# ART-Pi_H750_Peripherals.net
KiCad netlist of a schematic drawn in Altium Designer
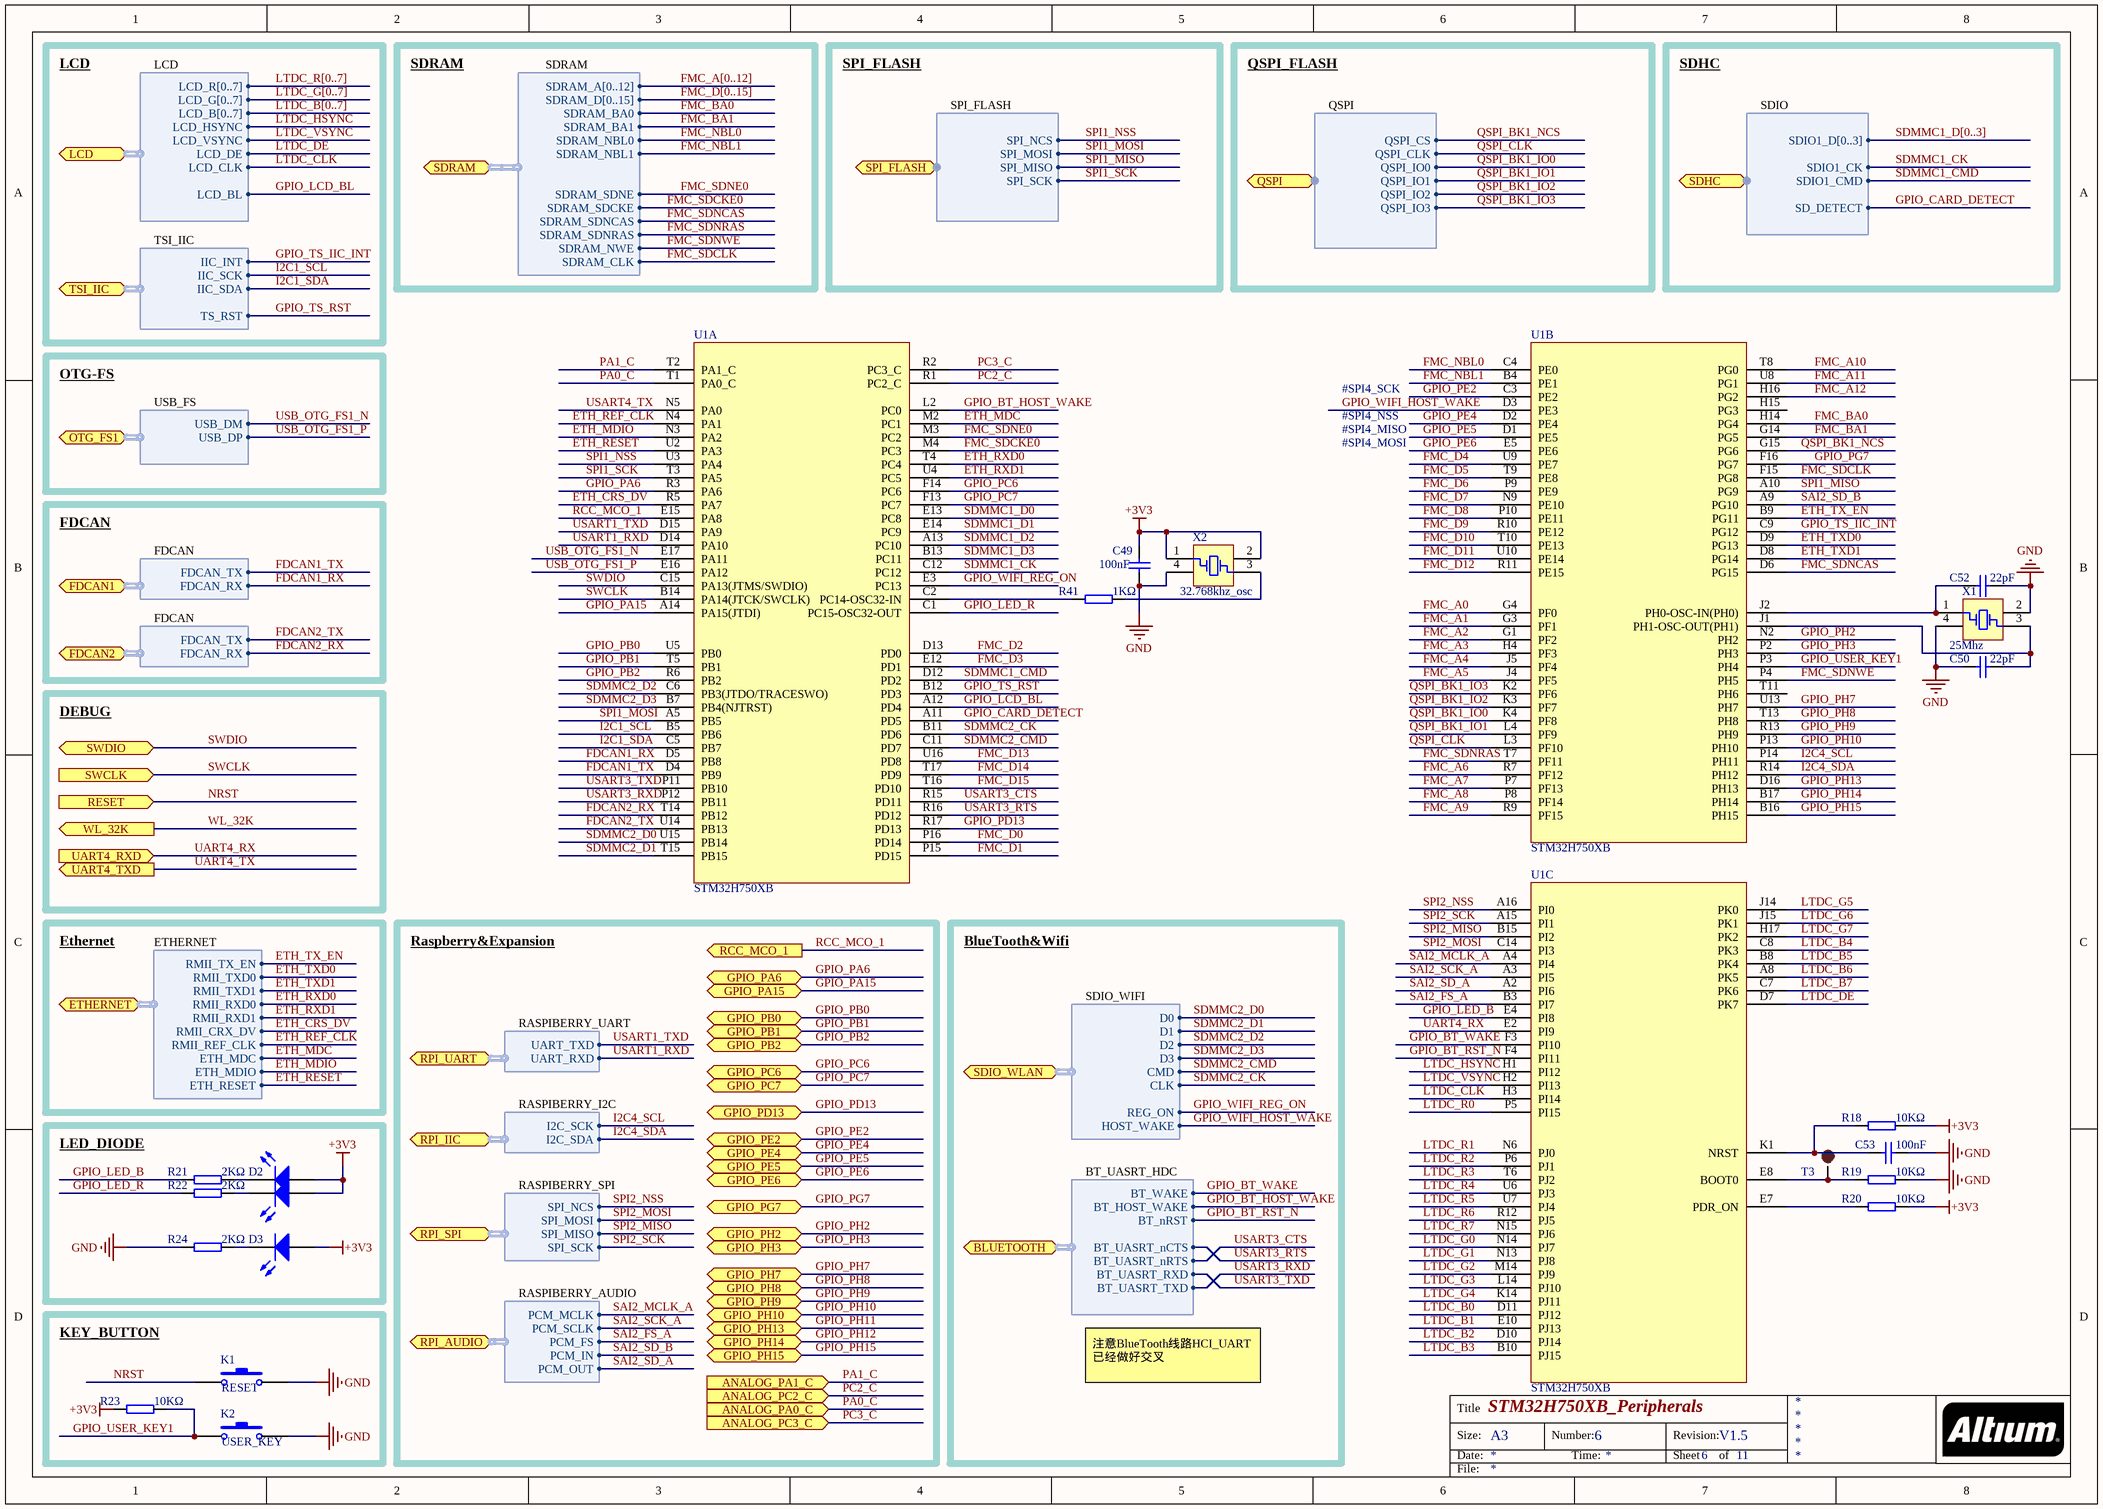
[diagram p0: ART-Pi_H750_Peripherals.SchDoc]

(export (version "E")
  (design (tool "Eeschema 10.0.6"))
  (components
    (comp (ref "C49")
      (value "100nF")
      (footprint "0402_C")
      (description "Capacitor")
      (fields (field (name "PUBLISHER") "Altium Limited"))
      (libsource (lib "ART-Pi_STM32H750_COPY") (part "Cap"))
    )
    (comp (ref "C50")
      (value "22pF")
      (footprint "0402_C")
      (description "Capacitor")
      (fields (field (name "PUBLISHER") "Altium Limited"))
      (libsource (lib "ART-Pi_STM32H750_COPY") (part "Cap"))
    )
    (comp (ref "C52")
      (value "22pF")
      (footprint "0402_C")
      (description "Capacitor")
      (fields (field (name "PUBLISHER") "Altium Limited"))
      (libsource (lib "ART-Pi_STM32H750_COPY") (part "Cap"))
    )
    (comp (ref "C53")
      (value "100nF")
      (footprint "0402_C")
      (description "Capacitor")
      (fields (field (name "PUBLISHER") "Altium Limited"))
      (libsource (lib "ART-Pi_STM32H750_COPY") (part "Cap"))
    )
    (comp (ref "D2")
      (value "LED2")
      (footprint "LED2-0603")
      (description "Typical RED, GREEN, YELLOW, AMBER GaAs LED")
      (fields (field (name "PUBLISHER") "Altium Limited"))
      (libsource (lib "ART-Pi_STM32H750_COPY") (part "LED2"))
    )
    (comp (ref "D3")
      (value "LED")
      (footprint "0603_LED")
      (description "Typical RED, GREEN, YELLOW, AMBER GaAs LED")
      (fields (field (name "PUBLISHER") "Altium Limited"))
      (libsource (lib "ART-Pi_STM32H750_COPY") (part "LED"))
    )
    (comp (ref "K1")
      (value "RESET")
      (footprint "SW-SMD")
      (description "Switch")
      (fields (field (name "PUBLISHER") "Altium Limited"))
      (libsource (lib "ART-Pi_STM32H750_COPY") (part "SW_PB"))
    )
    (comp (ref "K2")
      (value "USER_KEY")
      (footprint "SW-SMD")
      (description "Switch")
      (fields (field (name "PUBLISHER") "Altium Limited"))
      (libsource (lib "ART-Pi_STM32H750_COPY") (part "SW_PB"))
    )
    (comp (ref "R18")
      (value "10KΩ")
      (footprint "0402_R")
      (description "Resister")
      (libsource (lib "ART-Pi_STM32H750_COPY") (part "Res"))
    )
    (comp (ref "R19")
      (value "10KΩ")
      (footprint "0402_R")
      (description "Resister")
      (libsource (lib "ART-Pi_STM32H750_COPY") (part "Res"))
    )
    (comp (ref "R20")
      (value "10KΩ")
      (footprint "0402_R")
      (description "Resister")
      (libsource (lib "ART-Pi_STM32H750_COPY") (part "Res"))
    )
    (comp (ref "R21")
      (value "2KΩ")
      (footprint "0402_R")
      (description "Resister")
      (libsource (lib "ART-Pi_STM32H750_COPY") (part "Res"))
    )
    (comp (ref "R22")
      (value "2KΩ")
      (footprint "0402_R")
      (description "Resister")
      (libsource (lib "ART-Pi_STM32H750_COPY") (part "Res"))
    )
    (comp (ref "R23")
      (value "10KΩ")
      (footprint "0402_R")
      (description "Resister")
      (libsource (lib "ART-Pi_STM32H750_COPY") (part "Res"))
    )
    (comp (ref "R24")
      (value "2KΩ")
      (footprint "0402_R")
      (description "Resister")
      (libsource (lib "ART-Pi_STM32H750_COPY") (part "Res"))
    )
    (comp (ref "R41")
      (value "1KΩ")
      (footprint "0402_R")
      (description "Resister")
      (libsource (lib "ART-Pi_STM32H750_COPY") (part "Res"))
    )
    (comp (ref "T3")
      (value "TEST POINT")
      (footprint "Test_Point")
      (description "测试点")
      (libsource (lib "ART-Pi_STM32H750_COPY") (part "TEST-POINT"))
    )
    (comp (ref "U1")
      (value "STM32H750XB")
      (footprint "TFBGA240+25")
      (libsource (lib "ART-Pi_STM32H750_COPY") (part "STM32H750XB"))
    )
    (comp (ref "X1")
      (value "25Mhz")
      (footprint "SMD2520")
      (description "Crystal Oscillator")
      (fields (field (name "PUBLISHER") "Altium Limited"))
      (libsource (lib "ART-Pi_STM32H750_COPY") (part "XTAL_3225"))
    )
    (comp (ref "X2")
      (value "32.768khz_osc")
      (footprint "SMD2520")
      (description "Crystal Oscillator")
      (fields (field (name "PUBLISHER") "Altium Limited"))
      (libsource (lib "ART-Pi_STM32H750_COPY") (part "XTAL_3225"))
    )
  )
  (nets
    (net (code "3") (name "+3V3") (class "Default")
      (node (ref "C49") (pin "2") (pinfunction "2_2") (pintype "passive"))
      (node (ref "D2") (pin "1") (pinfunction "1_1") (pintype "passive"))
      (node (ref "D2") (pin "4") (pinfunction "4_4") (pintype "passive"))
      (node (ref "D3") (pin "1") (pinfunction "A_1") (pintype "passive"))
      (node (ref "R18") (pin "1") (pinfunction "1_1") (pintype "passive"))
      (node (ref "R20") (pin "1") (pinfunction "1_1") (pintype "passive"))
      (node (ref "R23") (pin "2") (pinfunction "2_2") (pintype "passive"))
      (node (ref "X2") (pin "1") (pinfunction "OSC1_1") (pintype "passive"))
      (node (ref "X2") (pin "2") (pinfunction "OSC2_2") (pintype "passive"))
    )
    (net (code "4") (name "/ETH_CRS_DV") (class "Default")
      (node (ref "U1") (pin "R5") (pinfunction "PA7_R5") (pintype "passive"))
    )
    (net (code "5") (name "/ETH_MDC") (class "Default")
      (node (ref "U1") (pin "M2") (pinfunction "PC1_M2") (pintype "passive"))
    )
    (net (code "6") (name "/ETH_MDIO") (class "Default")
      (node (ref "U1") (pin "N3") (pinfunction "PA2_N3") (pintype "passive"))
    )
    (net (code "7") (name "/ETH_REF_CLK") (class "Default")
      (node (ref "U1") (pin "N4") (pinfunction "PA1_N4") (pintype "passive"))
    )
    (net (code "8") (name "/ETH_RESET") (class "Default")
      (node (ref "U1") (pin "U2") (pinfunction "PA3_U2") (pintype "passive"))
    )
    (net (code "9") (name "/ETH_RXD0") (class "Default")
      (node (ref "U1") (pin "T4") (pinfunction "PC4_T4") (pintype "passive"))
    )
    (net (code "10") (name "/ETH_RXD1") (class "Default")
      (node (ref "U1") (pin "U4") (pinfunction "PC5_U4") (pintype "passive"))
    )
    (net (code "11") (name "/ETH_TXD0") (class "Default")
      (node (ref "U1") (pin "D9") (pinfunction "PG13_D9") (pintype "passive"))
    )
    (net (code "12") (name "/ETH_TXD1") (class "Default")
      (node (ref "U1") (pin "D8") (pinfunction "PG14_D8") (pintype "passive"))
    )
    (net (code "13") (name "/ETH_TX_EN") (class "Default")
      (node (ref "U1") (pin "B9") (pinfunction "PG11_B9") (pintype "passive"))
    )
    (net (code "14") (name "/FDCAN1_RX") (class "Default")
      (node (ref "U1") (pin "D5") (pinfunction "PB8_D5") (pintype "passive"))
    )
    (net (code "15") (name "/FDCAN1_TX") (class "Default")
      (node (ref "U1") (pin "D4") (pinfunction "PB9_D4") (pintype "passive"))
    )
    (net (code "16") (name "/FDCAN2_RX") (class "Default")
      (node (ref "U1") (pin "T14") (pinfunction "PB12_T14") (pintype "passive"))
    )
    (net (code "17") (name "/FDCAN2_TX") (class "Default")
      (node (ref "U1") (pin "U14") (pinfunction "PB13_U14") (pintype "passive"))
    )
    (net (code "18") (name "/FMC_A0") (class "Default")
      (node (ref "U1") (pin "G4") (pinfunction "PF0_G4") (pintype "passive"))
    )
    (net (code "19") (name "/FMC_A1") (class "Default")
      (node (ref "U1") (pin "G3") (pinfunction "PF1_G3") (pintype "passive"))
    )
    (net (code "20") (name "/FMC_A2") (class "Default")
      (node (ref "U1") (pin "G1") (pinfunction "PF2_G1") (pintype "passive"))
    )
    (net (code "21") (name "/FMC_A3") (class "Default")
      (node (ref "U1") (pin "H4") (pinfunction "PF3_H4") (pintype "passive"))
    )
    (net (code "22") (name "/FMC_A4") (class "Default")
      (node (ref "U1") (pin "J5") (pinfunction "PF4_J5") (pintype "passive"))
    )
    (net (code "23") (name "/FMC_A5") (class "Default")
      (node (ref "U1") (pin "J4") (pinfunction "PF5_J4") (pintype "passive"))
    )
    (net (code "24") (name "/FMC_A6") (class "Default")
      (node (ref "U1") (pin "R7") (pinfunction "PF12_R7") (pintype "passive"))
    )
    (net (code "25") (name "/FMC_A7") (class "Default")
      (node (ref "U1") (pin "P7") (pinfunction "PF13_P7") (pintype "passive"))
    )
    (net (code "26") (name "/FMC_A8") (class "Default")
      (node (ref "U1") (pin "P8") (pinfunction "PF14_P8") (pintype "passive"))
    )
    (net (code "27") (name "/FMC_A9") (class "Default")
      (node (ref "U1") (pin "R9") (pinfunction "PF15_R9") (pintype "passive"))
    )
    (net (code "28") (name "/FMC_A10") (class "Default")
      (node (ref "U1") (pin "T8") (pinfunction "PG0_T8") (pintype "passive"))
    )
    (net (code "29") (name "/FMC_A11") (class "Default")
      (node (ref "U1") (pin "U8") (pinfunction "PG1_U8") (pintype "passive"))
    )
    (net (code "30") (name "/FMC_A12") (class "Default")
      (node (ref "U1") (pin "H16") (pinfunction "PG2_H16") (pintype "passive"))
    )
    (net (code "32") (name "/FMC_BA0") (class "Default")
      (node (ref "U1") (pin "H14") (pinfunction "PG4_H14") (pintype "passive"))
    )
    (net (code "33") (name "/FMC_BA1") (class "Default")
      (node (ref "U1") (pin "G14") (pinfunction "PG5_G14") (pintype "passive"))
    )
    (net (code "34") (name "/FMC_D0") (class "Default")
      (node (ref "U1") (pin "P16") (pinfunction "PD14_P16") (pintype "passive"))
    )
    (net (code "35") (name "/FMC_D1") (class "Default")
      (node (ref "U1") (pin "P15") (pinfunction "PD15_P15") (pintype "passive"))
    )
    (net (code "36") (name "/FMC_D2") (class "Default")
      (node (ref "U1") (pin "D13") (pinfunction "PD0_D13") (pintype "passive"))
    )
    (net (code "37") (name "/FMC_D3") (class "Default")
      (node (ref "U1") (pin "E12") (pinfunction "PD1_E12") (pintype "passive"))
    )
    (net (code "38") (name "/FMC_D4") (class "Default")
      (node (ref "U1") (pin "U9") (pinfunction "PE7_U9") (pintype "passive"))
    )
    (net (code "39") (name "/FMC_D5") (class "Default")
      (node (ref "U1") (pin "T9") (pinfunction "PE8_T9") (pintype "passive"))
    )
    (net (code "40") (name "/FMC_D6") (class "Default")
      (node (ref "U1") (pin "P9") (pinfunction "PE9_P9") (pintype "passive"))
    )
    (net (code "41") (name "/FMC_D7") (class "Default")
      (node (ref "U1") (pin "N9") (pinfunction "PE10_N9") (pintype "passive"))
    )
    (net (code "42") (name "/FMC_D8") (class "Default")
      (node (ref "U1") (pin "P10") (pinfunction "PE11_P10") (pintype "passive"))
    )
    (net (code "43") (name "/FMC_D9") (class "Default")
      (node (ref "U1") (pin "R10") (pinfunction "PE12_R10") (pintype "passive"))
    )
    (net (code "44") (name "/FMC_D10") (class "Default")
      (node (ref "U1") (pin "T10") (pinfunction "PE13_T10") (pintype "passive"))
    )
    (net (code "45") (name "/FMC_D11") (class "Default")
      (node (ref "U1") (pin "U10") (pinfunction "PE14_U10") (pintype "passive"))
    )
    (net (code "46") (name "/FMC_D12") (class "Default")
      (node (ref "U1") (pin "R11") (pinfunction "PE15_R11") (pintype "passive"))
    )
    (net (code "47") (name "/FMC_D13") (class "Default")
      (node (ref "U1") (pin "U16") (pinfunction "PD8_U16") (pintype "passive"))
    )
    (net (code "48") (name "/FMC_D14") (class "Default")
      (node (ref "U1") (pin "T17") (pinfunction "PD9_T17") (pintype "passive"))
    )
    (net (code "49") (name "/FMC_D15") (class "Default")
      (node (ref "U1") (pin "T16") (pinfunction "PD10_T16") (pintype "passive"))
    )
    (net (code "51") (name "/FMC_NBL0") (class "Default")
      (node (ref "U1") (pin "C4") (pinfunction "PE0_C4") (pintype "passive"))
    )
    (net (code "52") (name "/FMC_NBL1") (class "Default")
      (node (ref "U1") (pin "B4") (pinfunction "PE1_B4") (pintype "passive"))
    )
    (net (code "53") (name "/FMC_SDCKE0") (class "Default")
      (node (ref "U1") (pin "M4") (pinfunction "PC3_M4") (pintype "passive"))
    )
    (net (code "54") (name "/FMC_SDCLK") (class "Default")
      (node (ref "U1") (pin "F15") (pinfunction "PG8_F15") (pintype "passive"))
    )
    (net (code "55") (name "/FMC_SDNCAS") (class "Default")
      (node (ref "U1") (pin "D6") (pinfunction "PG15_D6") (pintype "passive"))
    )
    (net (code "56") (name "/FMC_SDNE0") (class "Default")
      (node (ref "U1") (pin "M3") (pinfunction "PC2_M3") (pintype "passive"))
    )
    (net (code "57") (name "/FMC_SDNRAS") (class "Default")
      (node (ref "U1") (pin "T7") (pinfunction "PF11_T7") (pintype "passive"))
    )
    (net (code "58") (name "/FMC_SDNWE") (class "Default")
      (node (ref "U1") (pin "P4") (pinfunction "PH5_P4") (pintype "passive"))
    )
    (net (code "59") (name "/GPIO_BT_HOST_WAKE") (class "Default")
      (node (ref "U1") (pin "L2") (pinfunction "PC0_L2") (pintype "passive"))
    )
    (net (code "60") (name "/GPIO_BT_RST_N") (class "Default")
      (node (ref "U1") (pin "F4") (pinfunction "PI11_F4") (pintype "passive"))
    )
    (net (code "61") (name "/GPIO_BT_WAKE") (class "Default")
      (node (ref "U1") (pin "F3") (pinfunction "PI10_F3") (pintype "passive"))
    )
    (net (code "62") (name "/GPIO_CARD_DETECT") (class "Default")
      (node (ref "U1") (pin "A11") (pinfunction "PD5_A11") (pintype "passive"))
    )
    (net (code "63") (name "/GPIO_LCD_BL") (class "Default")
      (node (ref "U1") (pin "A12") (pinfunction "PD4_A12") (pintype "passive"))
    )
    (net (code "64") (name "/GPIO_LED_B") (class "Default")
      (node (ref "R21") (pin "2") (pinfunction "2_2") (pintype "passive"))
      (node (ref "U1") (pin "E4") (pinfunction "PI8_E4") (pintype "passive"))
    )
    (net (code "65") (name "/GPIO_LED_R") (class "Default")
      (node (ref "R22") (pin "2") (pinfunction "2_2") (pintype "passive"))
      (node (ref "U1") (pin "C1") (pinfunction "PC15-OSC32-OUT_C1") (pintype "passive"))
    )
    (net (code "66") (name "/GPIO_PA6") (class "Default")
      (node (ref "U1") (pin "R3") (pinfunction "PA6_R3") (pintype "passive"))
    )
    (net (code "67") (name "/GPIO_PA15") (class "Default")
      (node (ref "U1") (pin "A14") (pinfunction "PA15(JTDI)_A14") (pintype "passive"))
    )
    (net (code "68") (name "/GPIO_PB0") (class "Default")
      (node (ref "U1") (pin "U5") (pinfunction "PB0_U5") (pintype "passive"))
    )
    (net (code "69") (name "/GPIO_PB1") (class "Default")
      (node (ref "U1") (pin "T5") (pinfunction "PB1_T5") (pintype "passive"))
    )
    (net (code "70") (name "/GPIO_PB2") (class "Default")
      (node (ref "U1") (pin "R6") (pinfunction "PB2_R6") (pintype "passive"))
    )
    (net (code "71") (name "/GPIO_PC6") (class "Default")
      (node (ref "U1") (pin "F14") (pinfunction "PC6_F14") (pintype "passive"))
    )
    (net (code "72") (name "/GPIO_PC7") (class "Default")
      (node (ref "U1") (pin "F13") (pinfunction "PC7_F13") (pintype "passive"))
    )
    (net (code "73") (name "/GPIO_PD13") (class "Default")
      (node (ref "U1") (pin "R17") (pinfunction "PD13_R17") (pintype "passive"))
    )
    (net (code "74") (name "/GPIO_PE2") (class "Default")
      (node (ref "U1") (pin "C3") (pinfunction "PE2_C3") (pintype "passive"))
    )
    (net (code "75") (name "/GPIO_PE4") (class "Default")
      (node (ref "U1") (pin "D2") (pinfunction "PE4_D2") (pintype "passive"))
    )
    (net (code "76") (name "/GPIO_PE5") (class "Default")
      (node (ref "U1") (pin "D1") (pinfunction "PE5_D1") (pintype "passive"))
    )
    (net (code "77") (name "/GPIO_PE6") (class "Default")
      (node (ref "U1") (pin "E5") (pinfunction "PE6_E5") (pintype "passive"))
    )
    (net (code "78") (name "/GPIO_PG7") (class "Default")
      (node (ref "U1") (pin "F16") (pinfunction "PG7_F16") (pintype "passive"))
    )
    (net (code "79") (name "/GPIO_PH2") (class "Default")
      (node (ref "U1") (pin "N2") (pinfunction "PH2_N2") (pintype "passive"))
    )
    (net (code "80") (name "/GPIO_PH3") (class "Default")
      (node (ref "U1") (pin "P2") (pinfunction "PH3_P2") (pintype "passive"))
    )
    (net (code "81") (name "/GPIO_PH7") (class "Default")
      (node (ref "U1") (pin "U13") (pinfunction "PH7_U13") (pintype "passive"))
    )
    (net (code "82") (name "/GPIO_PH8") (class "Default")
      (node (ref "U1") (pin "T13") (pinfunction "PH8_T13") (pintype "passive"))
    )
    (net (code "83") (name "/GPIO_PH9") (class "Default")
      (node (ref "U1") (pin "R13") (pinfunction "PH9_R13") (pintype "passive"))
    )
    (net (code "84") (name "/GPIO_PH10") (class "Default")
      (node (ref "U1") (pin "P13") (pinfunction "PH10_P13") (pintype "passive"))
    )
    (net (code "85") (name "/GPIO_PH11") (class "Default")
      (node (ref "U1") (pin "D16") (pinfunction "PH13_D16") (pintype "passive"))
    )
    (net (code "86") (name "/GPIO_PH12") (class "Default")
      (node (ref "U1") (pin "B17") (pinfunction "PH14_B17") (pintype "passive"))
    )
    (net (code "87") (name "/GPIO_PH15") (class "Default")
      (node (ref "U1") (pin "B16") (pinfunction "PH15_B16") (pintype "passive"))
    )
    (net (code "88") (name "/GPIO_TS_IIC_INT") (class "Default")
      (node (ref "U1") (pin "C9") (pinfunction "PG12_C9") (pintype "passive"))
    )
    (net (code "89") (name "/GPIO_TS_RST") (class "Default")
      (node (ref "U1") (pin "B12") (pinfunction "PD3_B12") (pintype "passive"))
    )
    (net (code "90") (name "/GPIO_USER_KEY1") (class "Default")
      (node (ref "K2") (pin "1") (pinfunction "1_1") (pintype "passive"))
      (node (ref "R23") (pin "1") (pinfunction "1_1") (pintype "passive"))
      (node (ref "U1") (pin "P3") (pinfunction "PH4_P3") (pintype "passive"))
    )
    (net (code "91") (name "/GPIO_WIFI_HOST_WAKE") (class "Default")
      (node (ref "U1") (pin "D3") (pinfunction "PE3_D3") (pintype "passive"))
    )
    (net (code "92") (name "/GPIO_WIFI_REG_ON") (class "Default")
      (node (ref "U1") (pin "E3") (pinfunction "PC13_E3") (pintype "passive"))
    )
    (net (code "93") (name "/I2C1_SCL") (class "Default")
      (node (ref "U1") (pin "B5") (pinfunction "PB6_B5") (pintype "passive"))
    )
    (net (code "94") (name "/I2C1_SDA") (class "Default")
      (node (ref "U1") (pin "C5") (pinfunction "PB7_C5") (pintype "passive"))
    )
    (net (code "95") (name "/I2C4_SCL") (class "Default")
      (node (ref "U1") (pin "P14") (pinfunction "PH11_P14") (pintype "passive"))
    )
    (net (code "96") (name "/I2C4_SDA") (class "Default")
      (node (ref "U1") (pin "R14") (pinfunction "PH12_R14") (pintype "passive"))
    )
    (net (code "97") (name "/LTDC_B0") (class "Default")
      (node (ref "U1") (pin "D11") (pinfunction "PJ12_D11") (pintype "passive"))
    )
    (net (code "98") (name "/LTDC_B1") (class "Default")
      (node (ref "U1") (pin "E10") (pinfunction "PJ13_E10") (pintype "passive"))
    )
    (net (code "99") (name "/LTDC_B2") (class "Default")
      (node (ref "U1") (pin "D10") (pinfunction "PJ14_D10") (pintype "passive"))
    )
    (net (code "100") (name "/LTDC_B3") (class "Default")
      (node (ref "U1") (pin "B10") (pinfunction "PJ15_B10") (pintype "passive"))
    )
    (net (code "101") (name "/LTDC_B4") (class "Default")
      (node (ref "U1") (pin "C8") (pinfunction "PK3_C8") (pintype "passive"))
    )
    (net (code "102") (name "/LTDC_B5") (class "Default")
      (node (ref "U1") (pin "B8") (pinfunction "PK4_B8") (pintype "passive"))
    )
    (net (code "103") (name "/LTDC_B6") (class "Default")
      (node (ref "U1") (pin "A8") (pinfunction "PK5_A8") (pintype "passive"))
    )
    (net (code "104") (name "/LTDC_B7") (class "Default")
      (node (ref "U1") (pin "C7") (pinfunction "PK6_C7") (pintype "passive"))
    )
    (net (code "106") (name "/LTDC_CLK") (class "Default")
      (node (ref "U1") (pin "H3") (pinfunction "PI14_H3") (pintype "passive"))
    )
    (net (code "107") (name "/LTDC_DE") (class "Default")
      (node (ref "U1") (pin "D7") (pinfunction "PK7_D7") (pintype "passive"))
    )
    (net (code "108") (name "/LTDC_G0") (class "Default")
      (node (ref "U1") (pin "N14") (pinfunction "PJ7_N14") (pintype "passive"))
    )
    (net (code "109") (name "/LTDC_G1") (class "Default")
      (node (ref "U1") (pin "N13") (pinfunction "PJ8_N13") (pintype "passive"))
    )
    (net (code "110") (name "/LTDC_G2") (class "Default")
      (node (ref "U1") (pin "M14") (pinfunction "PJ9_M14") (pintype "passive"))
    )
    (net (code "111") (name "/LTDC_G3") (class "Default")
      (node (ref "U1") (pin "L14") (pinfunction "PJ10_L14") (pintype "passive"))
    )
    (net (code "112") (name "/LTDC_G4") (class "Default")
      (node (ref "U1") (pin "K14") (pinfunction "PJ11_K14") (pintype "passive"))
    )
    (net (code "113") (name "/LTDC_G5") (class "Default")
      (node (ref "U1") (pin "J14") (pinfunction "PK0_J14") (pintype "passive"))
    )
    (net (code "114") (name "/LTDC_G6") (class "Default")
      (node (ref "U1") (pin "J15") (pinfunction "PK1_J15") (pintype "passive"))
    )
    (net (code "115") (name "/LTDC_G7") (class "Default")
      (node (ref "U1") (pin "H17") (pinfunction "PK2_H17") (pintype "passive"))
    )
    (net (code "117") (name "/LTDC_HSYNC") (class "Default")
      (node (ref "U1") (pin "H1") (pinfunction "PI12_H1") (pintype "passive"))
    )
    (net (code "118") (name "/LTDC_R0") (class "Default")
      (node (ref "U1") (pin "P5") (pinfunction "PI15_P5") (pintype "passive"))
    )
    (net (code "119") (name "/LTDC_R1") (class "Default")
      (node (ref "U1") (pin "N6") (pinfunction "PJ0_N6") (pintype "passive"))
    )
    (net (code "120") (name "/LTDC_R2") (class "Default")
      (node (ref "U1") (pin "P6") (pinfunction "PJ1_P6") (pintype "passive"))
    )
    (net (code "121") (name "/LTDC_R3") (class "Default")
      (node (ref "U1") (pin "T6") (pinfunction "PJ2_T6") (pintype "passive"))
    )
    (net (code "122") (name "/LTDC_R4") (class "Default")
      (node (ref "U1") (pin "U6") (pinfunction "PJ3_U6") (pintype "passive"))
    )
    (net (code "123") (name "/LTDC_R5") (class "Default")
      (node (ref "U1") (pin "U7") (pinfunction "PJ4_U7") (pintype "passive"))
    )
    (net (code "124") (name "/LTDC_R6") (class "Default")
      (node (ref "U1") (pin "R12") (pinfunction "PJ5_R12") (pintype "passive"))
    )
    (net (code "125") (name "/LTDC_R7") (class "Default")
      (node (ref "U1") (pin "N15") (pinfunction "PJ6_N15") (pintype "passive"))
    )
    (net (code "127") (name "/LTDC_VSYNC") (class "Default")
      (node (ref "U1") (pin "H2") (pinfunction "PI13_H2") (pintype "passive"))
    )
    (net (code "128") (name "/NRST") (class "Default")
      (node (ref "K1") (pin "1") (pinfunction "1_1") (pintype "passive"))
    )
    (net (code "129") (name "/PA0_C") (class "Default")
      (node (ref "U1") (pin "T1") (pinfunction "PA0_C_T1") (pintype "passive"))
    )
    (net (code "130") (name "/PA1_C") (class "Default")
      (node (ref "U1") (pin "T2") (pinfunction "PA1_C_T2") (pintype "passive"))
    )
    (net (code "131") (name "/PC2_C") (class "Default")
      (node (ref "U1") (pin "R1") (pinfunction "PC2_C_R1") (pintype "passive"))
    )
    (net (code "132") (name "/PC3_C") (class "Default")
      (node (ref "U1") (pin "R2") (pinfunction "PC3_C_R2") (pintype "passive"))
    )
    (net (code "133") (name "/QSPI_BK1_IO0") (class "Default")
      (node (ref "U1") (pin "K4") (pinfunction "PF8_K4") (pintype "passive"))
    )
    (net (code "134") (name "/QSPI_BK1_IO1") (class "Default")
      (node (ref "U1") (pin "L4") (pinfunction "PF9_L4") (pintype "passive"))
    )
    (net (code "135") (name "/QSPI_BK1_IO2") (class "Default")
      (node (ref "U1") (pin "K3") (pinfunction "PF7_K3") (pintype "passive"))
    )
    (net (code "136") (name "/QSPI_BK1_IO3") (class "Default")
      (node (ref "U1") (pin "K2") (pinfunction "PF6_K2") (pintype "passive"))
    )
    (net (code "137") (name "/QSPI_BK1_NCS") (class "Default")
      (node (ref "U1") (pin "G15") (pinfunction "PG6_G15") (pintype "passive"))
    )
    (net (code "138") (name "/QSPI_CLK") (class "Default")
      (node (ref "U1") (pin "L3") (pinfunction "PF10_L3") (pintype "passive"))
    )
    (net (code "139") (name "/RCC_MCO_1") (class "Default")
      (node (ref "U1") (pin "E15") (pinfunction "PA8_E15") (pintype "passive"))
    )
    (net (code "140") (name "/SAI2_FS_A") (class "Default")
      (node (ref "U1") (pin "B3") (pinfunction "PI7_B3") (pintype "passive"))
    )
    (net (code "141") (name "/SAI2_MCLK_A") (class "Default")
      (node (ref "U1") (pin "A4") (pinfunction "PI4_A4") (pintype "passive"))
    )
    (net (code "142") (name "/SAI2_SCK_A") (class "Default")
      (node (ref "U1") (pin "A3") (pinfunction "PI5_A3") (pintype "passive"))
    )
    (net (code "143") (name "/SAI2_SD_A") (class "Default")
      (node (ref "U1") (pin "A2") (pinfunction "PI6_A2") (pintype "passive"))
    )
    (net (code "144") (name "/SAI2_SD_B") (class "Default")
      (node (ref "U1") (pin "A9") (pinfunction "PG10_A9") (pintype "passive"))
    )
    (net (code "146") (name "/SDMMC1_CK") (class "Default")
      (node (ref "U1") (pin "C12") (pinfunction "PC12_C12") (pintype "passive"))
    )
    (net (code "147") (name "/SDMMC1_CMD") (class "Default")
      (node (ref "U1") (pin "D12") (pinfunction "PD2_D12") (pintype "passive"))
    )
    (net (code "148") (name "/SDMMC1_D0") (class "Default")
      (node (ref "U1") (pin "E13") (pinfunction "PC8_E13") (pintype "passive"))
    )
    (net (code "149") (name "/SDMMC1_D1") (class "Default")
      (node (ref "U1") (pin "E14") (pinfunction "PC9_E14") (pintype "passive"))
    )
    (net (code "150") (name "/SDMMC1_D2") (class "Default")
      (node (ref "U1") (pin "A13") (pinfunction "PC10_A13") (pintype "passive"))
    )
    (net (code "151") (name "/SDMMC1_D3") (class "Default")
      (node (ref "U1") (pin "B13") (pinfunction "PC11_B13") (pintype "passive"))
    )
    (net (code "152") (name "/SDMMC2_CK") (class "Default")
      (node (ref "U1") (pin "B11") (pinfunction "PD6_B11") (pintype "passive"))
    )
    (net (code "153") (name "/SDMMC2_CMD") (class "Default")
      (node (ref "U1") (pin "C11") (pinfunction "PD7_C11") (pintype "passive"))
    )
    (net (code "154") (name "/SDMMC2_D0") (class "Default")
      (node (ref "U1") (pin "U15") (pinfunction "PB14_U15") (pintype "passive"))
    )
    (net (code "155") (name "/SDMMC2_D1") (class "Default")
      (node (ref "U1") (pin "T15") (pinfunction "PB15_T15") (pintype "passive"))
    )
    (net (code "156") (name "/SDMMC2_D2") (class "Default")
      (node (ref "U1") (pin "C6") (pinfunction "PB3(JTDO/TRACESWO)_C6") (pintype "passive"))
    )
    (net (code "157") (name "/SDMMC2_D3") (class "Default")
      (node (ref "U1") (pin "B7") (pinfunction "PB4(NJTRST)_B7") (pintype "passive"))
    )
    (net (code "158") (name "/SPI1_MISO") (class "Default")
      (node (ref "U1") (pin "A10") (pinfunction "PG9_A10") (pintype "passive"))
    )
    (net (code "159") (name "/SPI1_MOSI") (class "Default")
      (node (ref "U1") (pin "A5") (pinfunction "PB5_A5") (pintype "passive"))
    )
    (net (code "160") (name "/SPI1_NSS") (class "Default")
      (node (ref "U1") (pin "U3") (pinfunction "PA4_U3") (pintype "passive"))
    )
    (net (code "161") (name "/SPI1_SCK") (class "Default")
      (node (ref "U1") (pin "T3") (pinfunction "PA5_T3") (pintype "passive"))
    )
    (net (code "162") (name "/SPI2_MISO") (class "Default")
      (node (ref "U1") (pin "B15") (pinfunction "PI2_B15") (pintype "passive"))
    )
    (net (code "163") (name "/SPI2_MOSI") (class "Default")
      (node (ref "U1") (pin "C14") (pinfunction "PI3_C14") (pintype "passive"))
    )
    (net (code "164") (name "/SPI2_NSS") (class "Default")
      (node (ref "U1") (pin "A16") (pinfunction "PI0_A16") (pintype "passive"))
    )
    (net (code "165") (name "/SPI2_SCK") (class "Default")
      (node (ref "U1") (pin "A15") (pinfunction "PI1_A15") (pintype "passive"))
    )
    (net (code "166") (name "/SWCLK") (class "Default")
      (node (ref "U1") (pin "B14") (pinfunction "PA14(JTCK/SWCLK)_B14") (pintype "passive"))
    )
    (net (code "167") (name "/SWDIO") (class "Default")
      (node (ref "U1") (pin "C15") (pinfunction "PA13(JTMS/SWDIO)_C15") (pintype "passive"))
    )
    (net (code "168") (name "/UART4_RX") (class "Default")
      (node (ref "U1") (pin "E2") (pinfunction "PI9_E2") (pintype "passive"))
    )
    (net (code "170") (name "/USART1_RXD") (class "Default")
      (node (ref "U1") (pin "D14") (pinfunction "PA10_D14") (pintype "passive"))
    )
    (net (code "171") (name "/USART1_TXD") (class "Default")
      (node (ref "U1") (pin "D15") (pinfunction "PA9_D15") (pintype "passive"))
    )
    (net (code "172") (name "/USART3_CTS") (class "Default")
      (node (ref "U1") (pin "R15") (pinfunction "PD11_R15") (pintype "passive"))
    )
    (net (code "173") (name "/USART3_RTS") (class "Default")
      (node (ref "U1") (pin "R16") (pinfunction "PD12_R16") (pintype "passive"))
    )
    (net (code "174") (name "/USART3_RXD") (class "Default")
      (node (ref "U1") (pin "P12") (pinfunction "PB11_P12") (pintype "passive"))
    )
    (net (code "175") (name "/USART3_TXD") (class "Default")
      (node (ref "U1") (pin "P11") (pinfunction "PB10_P11") (pintype "passive"))
    )
    (net (code "176") (name "/USART4_TX") (class "Default")
      (node (ref "U1") (pin "N5") (pinfunction "PA0_N5") (pintype "passive"))
    )
    (net (code "177") (name "/USB_OTG_FS1_N") (class "Default")
      (node (ref "U1") (pin "E17") (pinfunction "PA11_E17") (pintype "passive"))
    )
    (net (code "178") (name "/USB_OTG_FS1_P") (class "Default")
      (node (ref "U1") (pin "E16") (pinfunction "PA12_E16") (pintype "passive"))
    )
    (net (code "182") (name "GND") (class "Default")
      (node (ref "C49") (pin "1") (pinfunction "1_1") (pintype "passive"))
      (node (ref "C50") (pin "2") (pinfunction "2_2") (pintype "passive"))
      (node (ref "C52") (pin "1") (pinfunction "1_1") (pintype "passive"))
      (node (ref "C53") (pin "1") (pinfunction "1_1") (pintype "passive"))
      (node (ref "K1") (pin "2") (pinfunction "2_2") (pintype "passive"))
      (node (ref "K2") (pin "2") (pinfunction "2_2") (pintype "passive"))
      (node (ref "R19") (pin "1") (pinfunction "1_1") (pintype "passive"))
      (node (ref "R24") (pin "2") (pinfunction "2_2") (pintype "passive"))
      (node (ref "X1") (pin "2") (pinfunction "OSC2_2") (pintype "passive"))
      (node (ref "X1") (pin "4") (pinfunction "4_4") (pintype "passive"))
      (node (ref "X2") (pin "4") (pinfunction "4_4") (pintype "passive"))
    )
    (net (code "183") (name "Net-(D2-Pad2)") (class "Default")
      (node (ref "D2") (pin "2") (pinfunction "2_2") (pintype "passive"))
      (node (ref "R22") (pin "1") (pinfunction "1_1") (pintype "passive"))
    )
    (net (code "184") (name "Net-(D2-Pad3)") (class "Default")
      (node (ref "D2") (pin "3") (pinfunction "3_3") (pintype "passive"))
      (node (ref "R21") (pin "1") (pinfunction "1_1") (pintype "passive"))
    )
    (net (code "185") (name "Net-(D3-K)") (class "Default")
      (node (ref "D3") (pin "2") (pinfunction "K_2") (pintype "passive"))
      (node (ref "R24") (pin "1") (pinfunction "1_1") (pintype "passive"))
    )
    (net (code "186") (name "Net-(R41-Pad1)") (class "Default")
      (node (ref "R41") (pin "1") (pinfunction "1_1") (pintype "passive"))
      (node (ref "X2") (pin "3") (pinfunction "3_3") (pintype "passive"))
    )
    (net (code "187") (name "Net-(U1A-PC14-OSC32-IN)") (class "Default")
      (node (ref "R41") (pin "2") (pinfunction "2_2") (pintype "passive"))
      (node (ref "U1") (pin "C2") (pinfunction "PC14-OSC32-IN_C2") (pintype "passive"))
    )
    (net (code "188") (name "Net-(U1B-PH0-OSC-IN(PH0))") (class "Default")
      (node (ref "C52") (pin "2") (pinfunction "2_2") (pintype "passive"))
      (node (ref "U1") (pin "J2") (pinfunction "PH0-OSC-IN(PH0)_J2") (pintype "passive"))
      (node (ref "X1") (pin "1") (pinfunction "OSC1_1") (pintype "passive"))
    )
    (net (code "189") (name "Net-(U1B-PH1-OSC-OUT(PH1))") (class "Default")
      (node (ref "C50") (pin "1") (pinfunction "1_1") (pintype "passive"))
      (node (ref "U1") (pin "J1") (pinfunction "PH1-OSC-OUT(PH1)_J1") (pintype "passive"))
      (node (ref "X1") (pin "3") (pinfunction "3_3") (pintype "passive"))
    )
    (net (code "190") (name "Net-(U1C-BOOT0)") (class "Default")
      (node (ref "R19") (pin "2") (pinfunction "2_2") (pintype "passive"))
      (node (ref "T3") (pin "1") (pinfunction "1_1") (pintype "passive"))
      (node (ref "U1") (pin "E8") (pinfunction "BOOT0_E8") (pintype "passive"))
    )
    (net (code "191") (name "Net-(U1C-NRST)") (class "Default")
      (node (ref "C53") (pin "2") (pinfunction "2_2") (pintype "passive"))
      (node (ref "R18") (pin "2") (pinfunction "2_2") (pintype "passive"))
      (node (ref "U1") (pin "K1") (pinfunction "NRST_K1") (pintype "passive"))
    )
    (net (code "192") (name "Net-(U1C-PDR_ON)") (class "Default")
      (node (ref "R20") (pin "2") (pinfunction "2_2") (pintype "passive"))
      (node (ref "U1") (pin "E7") (pinfunction "PDR_ON_E7") (pintype "passive"))
    )
    (net (code "193") (name "unconnected-(U1B-PG3-PadH15)") (class "Default")
      (node (ref "U1") (pin "H15") (pinfunction "PG3_H15") (pintype "passive"))
    )
    (net (code "194") (name "unconnected-(U1B-PH6-PadT11)") (class "Default")
      (node (ref "U1") (pin "T11") (pinfunction "PH6_T11") (pintype "passive"))
    )
  )
)
